# P03_McuPower.net
KiCad netlist of a schematic drawn in Altium Designer
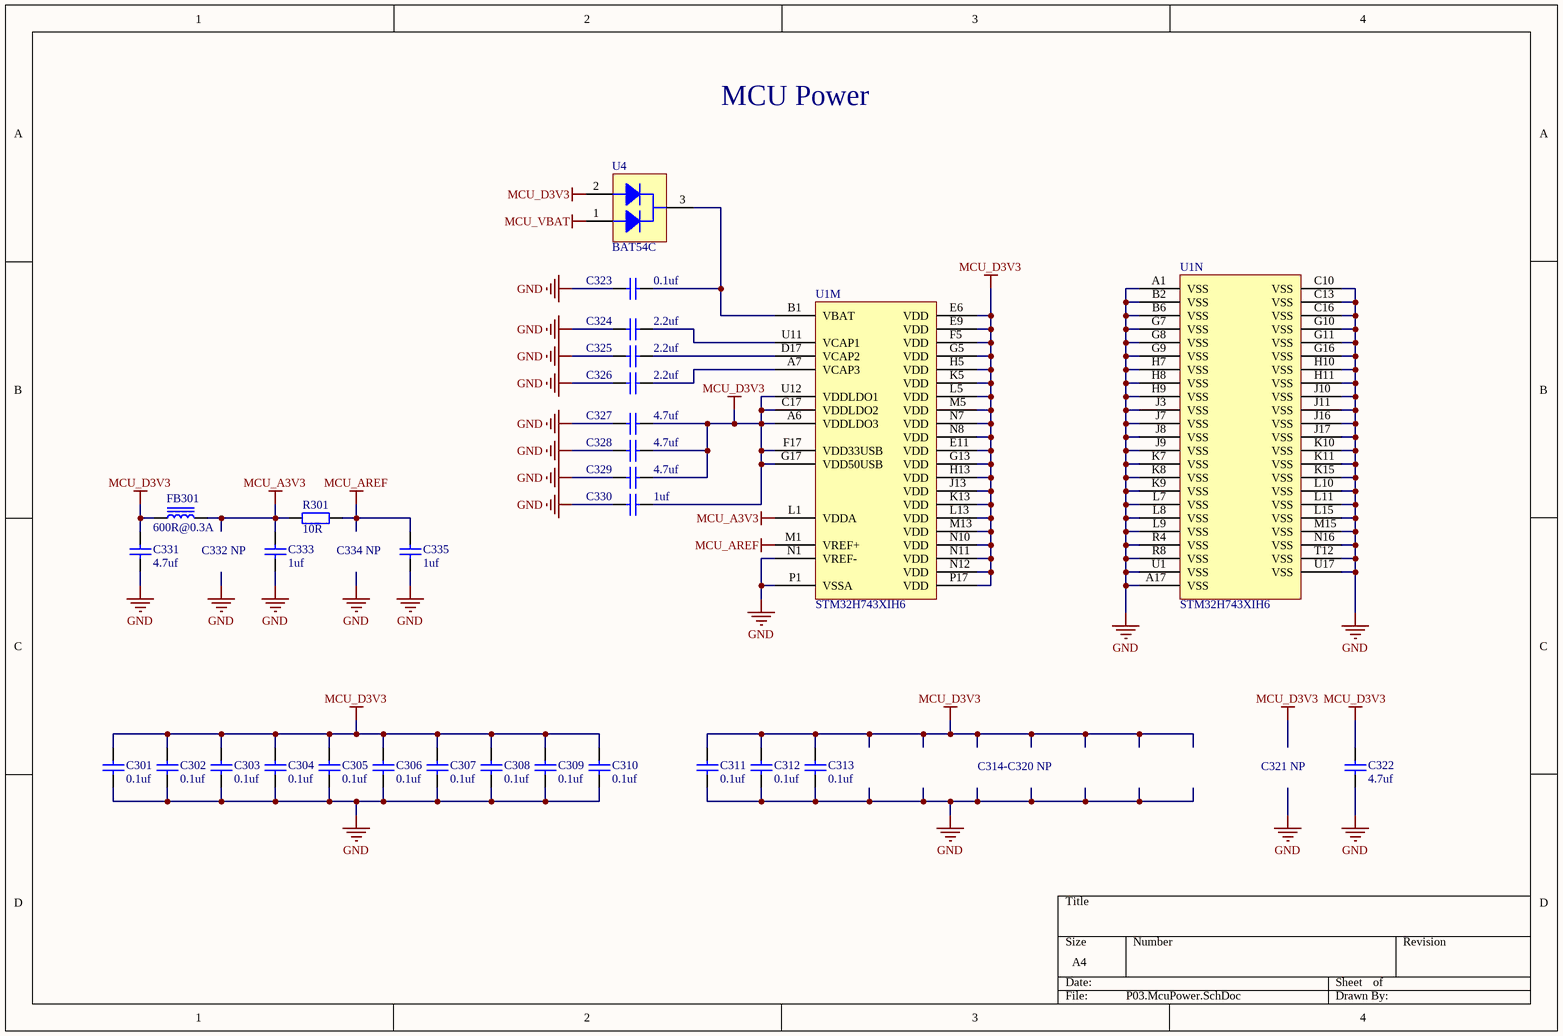
[diagram p0: P03.McuPower.SchDoc]

(export (version "E")
  (design (tool "Eeschema 10.0.6"))
  (components
    (comp (ref "C301")
      (value "0.1uf")
      (footprint "C0402")
      (fields (field (name "Comment") "Cap"))
      (libsource (lib "carrot_lib") (part "Cap"))
    )
    (comp (ref "C302")
      (value "0.1uf")
      (footprint "C0402")
      (fields (field (name "Comment") "Cap"))
      (libsource (lib "carrot_lib") (part "Cap"))
    )
    (comp (ref "C303")
      (value "0.1uf")
      (footprint "C0402")
      (fields (field (name "Comment") "Cap"))
      (libsource (lib "carrot_lib") (part "Cap"))
    )
    (comp (ref "C304")
      (value "0.1uf")
      (footprint "C0402")
      (fields (field (name "Comment") "Cap"))
      (libsource (lib "carrot_lib") (part "Cap"))
    )
    (comp (ref "C305")
      (value "0.1uf")
      (footprint "C0402")
      (fields (field (name "Comment") "Cap"))
      (libsource (lib "carrot_lib") (part "Cap"))
    )
    (comp (ref "C306")
      (value "0.1uf")
      (footprint "C0402")
      (fields (field (name "Comment") "Cap"))
      (libsource (lib "carrot_lib") (part "Cap"))
    )
    (comp (ref "C307")
      (value "0.1uf")
      (footprint "C0402")
      (fields (field (name "Comment") "Cap"))
      (libsource (lib "carrot_lib") (part "Cap"))
    )
    (comp (ref "C308")
      (value "0.1uf")
      (footprint "C0402")
      (fields (field (name "Comment") "Cap"))
      (libsource (lib "carrot_lib") (part "Cap"))
    )
    (comp (ref "C309")
      (value "0.1uf")
      (footprint "C0402")
      (fields (field (name "Comment") "Cap"))
      (libsource (lib "carrot_lib") (part "Cap"))
    )
    (comp (ref "C310")
      (value "0.1uf")
      (footprint "C0402")
      (fields (field (name "Comment") "Cap"))
      (libsource (lib "carrot_lib") (part "Cap"))
    )
    (comp (ref "C311")
      (value "0.1uf")
      (footprint "C0402")
      (fields (field (name "Comment") "Cap"))
      (libsource (lib "carrot_lib") (part "Cap"))
    )
    (comp (ref "C312")
      (value "0.1uf")
      (footprint "C0402")
      (fields (field (name "Comment") "Cap"))
      (libsource (lib "carrot_lib") (part "Cap"))
    )
    (comp (ref "C313")
      (value "0.1uf")
      (footprint "C0402")
      (fields (field (name "Comment") "Cap"))
      (libsource (lib "carrot_lib") (part "Cap"))
    )
    (comp (ref "C322")
      (value "4.7uf")
      (footprint "C0603")
      (fields (field (name "Comment") "Cap"))
      (libsource (lib "carrot_lib") (part "Cap"))
    )
    (comp (ref "C323")
      (value "0.1uf")
      (footprint "C0402")
      (fields (field (name "Comment") "Cap"))
      (libsource (lib "carrot_lib") (part "Cap"))
    )
    (comp (ref "C324")
      (value "2.2uf")
      (footprint "C0402")
      (fields (field (name "Comment") "Cap"))
      (libsource (lib "carrot_lib") (part "Cap"))
    )
    (comp (ref "C325")
      (value "2.2uf")
      (footprint "C0402")
      (fields (field (name "Comment") "Cap"))
      (libsource (lib "carrot_lib") (part "Cap"))
    )
    (comp (ref "C326")
      (value "2.2uf")
      (footprint "C0402")
      (fields (field (name "Comment") "Cap"))
      (libsource (lib "carrot_lib") (part "Cap"))
    )
    (comp (ref "C327")
      (value "4.7uf")
      (footprint "C0402")
      (fields (field (name "Comment") "Cap"))
      (libsource (lib "carrot_lib") (part "Cap"))
    )
    (comp (ref "C328")
      (value "4.7uf")
      (footprint "C0402")
      (fields (field (name "Comment") "Cap"))
      (libsource (lib "carrot_lib") (part "Cap"))
    )
    (comp (ref "C329")
      (value "4.7uf")
      (footprint "C0402")
      (fields (field (name "Comment") "Cap"))
      (libsource (lib "carrot_lib") (part "Cap"))
    )
    (comp (ref "C330")
      (value "1uf")
      (footprint "C0402")
      (fields (field (name "Comment") "Cap"))
      (libsource (lib "carrot_lib") (part "Cap"))
    )
    (comp (ref "C331")
      (value "4.7uf")
      (footprint "C0402")
      (fields (field (name "Comment") "Cap"))
      (libsource (lib "carrot_lib") (part "Cap"))
    )
    (comp (ref "C333")
      (value "1uf")
      (footprint "C0402")
      (fields (field (name "Comment") "Cap"))
      (libsource (lib "carrot_lib") (part "Cap"))
    )
    (comp (ref "C335")
      (value "1uf")
      (footprint "C0402")
      (fields (field (name "Comment") "Cap"))
      (libsource (lib "carrot_lib") (part "Cap"))
    )
    (comp (ref "FB301")
      (value "600R@0.3A")
      (footprint "FB0402")
      (description "Ferrite Bead")
      (libsource (lib "carrot_lib") (part "Ferrite Bead"))
    )
    (comp (ref "R301")
      (value "10R")
      (footprint "R0402")
      (description "电阻")
      (fields (field (name "Comment") "Res"))
      (libsource (lib "carrot_lib") (part "Res"))
    )
    (comp (ref "U1")
      (value "STM32H743XIH6")
      (footprint "STM32H743XIH6-TFBGA240+25")
      (description "32-bit Arm® Cortex®-M7 480MHz MCUs, up to 2MB Flash,up to 1MB RAM, 46 com. and analog interfaces")
      (libsource (lib "") (part "STM32H743XIH6_1"))
    )
    (comp (ref "U4")
      (value "BAT54C")
      (footprint "BAT54X-SOT23")
      (description "Schottky barrier diodes")
      (libsource (lib "carrot_lib") (part "BAT54C"))
    )
  )
  (nets
    (net (code "1") (name "GND") (class "Default")
      (node (ref "C301") (pin "1") (pinfunction "1_1") (pintype "passive"))
      (node (ref "C302") (pin "1") (pinfunction "1_1") (pintype "passive"))
      (node (ref "C303") (pin "1") (pinfunction "1_1") (pintype "passive"))
      (node (ref "C304") (pin "1") (pinfunction "1_1") (pintype "passive"))
      (node (ref "C305") (pin "1") (pinfunction "1_1") (pintype "passive"))
      (node (ref "C306") (pin "1") (pinfunction "1_1") (pintype "passive"))
      (node (ref "C307") (pin "1") (pinfunction "1_1") (pintype "passive"))
      (node (ref "C308") (pin "1") (pinfunction "1_1") (pintype "passive"))
      (node (ref "C309") (pin "1") (pinfunction "1_1") (pintype "passive"))
      (node (ref "C310") (pin "1") (pinfunction "1_1") (pintype "passive"))
      (node (ref "C311") (pin "1") (pinfunction "1_1") (pintype "passive"))
      (node (ref "C312") (pin "1") (pinfunction "1_1") (pintype "passive"))
      (node (ref "C313") (pin "1") (pinfunction "1_1") (pintype "passive"))
      (node (ref "C322") (pin "1") (pinfunction "1_1") (pintype "passive"))
      (node (ref "C323") (pin "1") (pinfunction "1_1") (pintype "passive"))
      (node (ref "C324") (pin "1") (pinfunction "1_1") (pintype "passive"))
      (node (ref "C325") (pin "1") (pinfunction "1_1") (pintype "passive"))
      (node (ref "C326") (pin "1") (pinfunction "1_1") (pintype "passive"))
      (node (ref "C327") (pin "1") (pinfunction "1_1") (pintype "passive"))
      (node (ref "C328") (pin "1") (pinfunction "1_1") (pintype "passive"))
      (node (ref "C329") (pin "1") (pinfunction "1_1") (pintype "passive"))
      (node (ref "C330") (pin "1") (pinfunction "1_1") (pintype "passive"))
      (node (ref "C331") (pin "1") (pinfunction "1_1") (pintype "passive"))
      (node (ref "C333") (pin "1") (pinfunction "1_1") (pintype "passive"))
      (node (ref "C335") (pin "1") (pinfunction "1_1") (pintype "passive"))
      (node (ref "U1") (pin "A1") (pinfunction "VSS_A1") (pintype "power_in"))
      (node (ref "U1") (pin "A17") (pinfunction "VSS_A17") (pintype "power_in"))
      (node (ref "U1") (pin "B2") (pinfunction "VSS_B2") (pintype "power_in"))
      (node (ref "U1") (pin "B6") (pinfunction "VSS_B6") (pintype "power_in"))
      (node (ref "U1") (pin "C10") (pinfunction "VSS_C10") (pintype "power_in"))
      (node (ref "U1") (pin "C13") (pinfunction "VSS_C13") (pintype "power_in"))
      (node (ref "U1") (pin "C16") (pinfunction "VSS_C16") (pintype "power_in"))
      (node (ref "U1") (pin "G10") (pinfunction "VSS_G10") (pintype "power_in"))
      (node (ref "U1") (pin "G11") (pinfunction "VSS_G11") (pintype "power_in"))
      (node (ref "U1") (pin "G16") (pinfunction "VSS_G16") (pintype "power_in"))
      (node (ref "U1") (pin "G7") (pinfunction "VSS_G7") (pintype "power_in"))
      (node (ref "U1") (pin "G8") (pinfunction "VSS_G8") (pintype "power_in"))
      (node (ref "U1") (pin "G9") (pinfunction "VSS_G9") (pintype "power_in"))
      (node (ref "U1") (pin "H10") (pinfunction "VSS_H10") (pintype "power_in"))
      (node (ref "U1") (pin "H11") (pinfunction "VSS_H11") (pintype "power_in"))
      (node (ref "U1") (pin "H7") (pinfunction "VSS_H7") (pintype "power_in"))
      (node (ref "U1") (pin "H8") (pinfunction "VSS_H8") (pintype "power_in"))
      (node (ref "U1") (pin "H9") (pinfunction "VSS_H9") (pintype "power_in"))
      (node (ref "U1") (pin "J10") (pinfunction "VSS_J10") (pintype "power_in"))
      (node (ref "U1") (pin "J11") (pinfunction "VSS_J11") (pintype "power_in"))
      (node (ref "U1") (pin "J16") (pinfunction "VSS_J16") (pintype "power_in"))
      (node (ref "U1") (pin "J17") (pinfunction "VSS_J17") (pintype "power_in"))
      (node (ref "U1") (pin "J3") (pinfunction "VSS_J3") (pintype "power_in"))
      (node (ref "U1") (pin "J7") (pinfunction "VSS_J7") (pintype "power_in"))
      (node (ref "U1") (pin "J8") (pinfunction "VSS_J8") (pintype "power_in"))
      (node (ref "U1") (pin "J9") (pinfunction "VSS_J9") (pintype "power_in"))
      (node (ref "U1") (pin "K10") (pinfunction "VSS_K10") (pintype "power_in"))
      (node (ref "U1") (pin "K11") (pinfunction "VSS_K11") (pintype "power_in"))
      (node (ref "U1") (pin "K15") (pinfunction "VSS_K15") (pintype "power_in"))
      (node (ref "U1") (pin "K7") (pinfunction "VSS_K7") (pintype "power_in"))
      (node (ref "U1") (pin "K8") (pinfunction "VSS_K8") (pintype "power_in"))
      (node (ref "U1") (pin "K9") (pinfunction "VSS_K9") (pintype "power_in"))
      (node (ref "U1") (pin "L10") (pinfunction "VSS_L10") (pintype "power_in"))
      (node (ref "U1") (pin "L11") (pinfunction "VSS_L11") (pintype "power_in"))
      (node (ref "U1") (pin "L15") (pinfunction "VSS_L15") (pintype "power_in"))
      (node (ref "U1") (pin "L7") (pinfunction "VSS_L7") (pintype "power_in"))
      (node (ref "U1") (pin "L8") (pinfunction "VSS_L8") (pintype "power_in"))
      (node (ref "U1") (pin "L9") (pinfunction "VSS_L9") (pintype "power_in"))
      (node (ref "U1") (pin "M15") (pinfunction "VSS_M15") (pintype "power_in"))
      (node (ref "U1") (pin "N1") (pinfunction "VREF-_N1") (pintype "power_in"))
      (node (ref "U1") (pin "N16") (pinfunction "VSS_N16") (pintype "power_in"))
      (node (ref "U1") (pin "P1") (pinfunction "VSSA_P1") (pintype "power_in"))
      (node (ref "U1") (pin "R4") (pinfunction "VSS_R4") (pintype "power_in"))
      (node (ref "U1") (pin "R8") (pinfunction "VSS_R8") (pintype "power_in"))
      (node (ref "U1") (pin "T12") (pinfunction "VSS_T12") (pintype "power_in"))
      (node (ref "U1") (pin "U1") (pinfunction "VSS_U1") (pintype "power_in"))
      (node (ref "U1") (pin "U17") (pinfunction "VSS_U17") (pintype "power_in"))
    )
    (net (code "2") (name "MCU_A3V3") (class "Default")
      (node (ref "C333") (pin "2") (pinfunction "2_2") (pintype "passive"))
      (node (ref "FB301") (pin "2") (pinfunction "2_2") (pintype "passive"))
      (node (ref "R301") (pin "1") (pinfunction "1_1") (pintype "passive"))
      (node (ref "U1") (pin "L1") (pinfunction "VDDA_L1") (pintype "power_in"))
    )
    (net (code "3") (name "MCU_AREF") (class "Default")
      (node (ref "C335") (pin "2") (pinfunction "2_2") (pintype "passive"))
      (node (ref "R301") (pin "2") (pinfunction "2_2") (pintype "passive"))
      (node (ref "U1") (pin "M1") (pinfunction "VREF+_M1") (pintype "power_in"))
    )
    (net (code "4") (name "MCU_D3V3") (class "Default")
      (node (ref "C301") (pin "2") (pinfunction "2_2") (pintype "passive"))
      (node (ref "C302") (pin "2") (pinfunction "2_2") (pintype "passive"))
      (node (ref "C303") (pin "2") (pinfunction "2_2") (pintype "passive"))
      (node (ref "C304") (pin "2") (pinfunction "2_2") (pintype "passive"))
      (node (ref "C305") (pin "2") (pinfunction "2_2") (pintype "passive"))
      (node (ref "C306") (pin "2") (pinfunction "2_2") (pintype "passive"))
      (node (ref "C307") (pin "2") (pinfunction "2_2") (pintype "passive"))
      (node (ref "C308") (pin "2") (pinfunction "2_2") (pintype "passive"))
      (node (ref "C309") (pin "2") (pinfunction "2_2") (pintype "passive"))
      (node (ref "C310") (pin "2") (pinfunction "2_2") (pintype "passive"))
      (node (ref "C311") (pin "2") (pinfunction "2_2") (pintype "passive"))
      (node (ref "C312") (pin "2") (pinfunction "2_2") (pintype "passive"))
      (node (ref "C313") (pin "2") (pinfunction "2_2") (pintype "passive"))
      (node (ref "C322") (pin "2") (pinfunction "2_2") (pintype "passive"))
      (node (ref "C327") (pin "2") (pinfunction "2_2") (pintype "passive"))
      (node (ref "C328") (pin "2") (pinfunction "2_2") (pintype "passive"))
      (node (ref "C329") (pin "2") (pinfunction "2_2") (pintype "passive"))
      (node (ref "C330") (pin "2") (pinfunction "2_2") (pintype "passive"))
      (node (ref "C331") (pin "2") (pinfunction "2_2") (pintype "passive"))
      (node (ref "FB301") (pin "1") (pinfunction "1_1") (pintype "passive"))
      (node (ref "U1") (pin "A6") (pinfunction "VDDLDO3_A6") (pintype "power_in"))
      (node (ref "U1") (pin "C17") (pinfunction "VDDLDO2_C17") (pintype "power_in"))
      (node (ref "U1") (pin "E11") (pinfunction "VDD_E11") (pintype "power_in"))
      (node (ref "U1") (pin "E6") (pinfunction "VDD_E6") (pintype "power_in"))
      (node (ref "U1") (pin "E9") (pinfunction "VDD_E9") (pintype "power_in"))
      (node (ref "U1") (pin "F17") (pinfunction "VDD33USB_F17") (pintype "power_in"))
      (node (ref "U1") (pin "F5") (pinfunction "VDD_F5") (pintype "power_in"))
      (node (ref "U1") (pin "G13") (pinfunction "VDD_G13") (pintype "power_in"))
      (node (ref "U1") (pin "G17") (pinfunction "VDD50USB_G17") (pintype "power_in"))
      (node (ref "U1") (pin "G5") (pinfunction "VDD_G5") (pintype "power_in"))
      (node (ref "U1") (pin "H13") (pinfunction "VDD_H13") (pintype "power_in"))
      (node (ref "U1") (pin "H5") (pinfunction "VDD_H5") (pintype "power_in"))
      (node (ref "U1") (pin "J13") (pinfunction "VDD_J13") (pintype "power_in"))
      (node (ref "U1") (pin "K13") (pinfunction "VDD_K13") (pintype "power_in"))
      (node (ref "U1") (pin "K5") (pinfunction "VDD_K5") (pintype "power_in"))
      (node (ref "U1") (pin "L13") (pinfunction "VDD_L13") (pintype "power_in"))
      (node (ref "U1") (pin "L5") (pinfunction "VDD_L5") (pintype "power_in"))
      (node (ref "U1") (pin "M13") (pinfunction "VDD_M13") (pintype "power_in"))
      (node (ref "U1") (pin "M5") (pinfunction "VDD_M5") (pintype "power_in"))
      (node (ref "U1") (pin "N10") (pinfunction "VDD_N10") (pintype "power_in"))
      (node (ref "U1") (pin "N11") (pinfunction "VDD_N11") (pintype "power_in"))
      (node (ref "U1") (pin "N12") (pinfunction "VDD_N12") (pintype "power_in"))
      (node (ref "U1") (pin "N7") (pinfunction "VDD_N7") (pintype "power_in"))
      (node (ref "U1") (pin "N8") (pinfunction "VDD_N8") (pintype "power_in"))
      (node (ref "U1") (pin "P17") (pinfunction "VDD_P17") (pintype "power_in"))
      (node (ref "U1") (pin "U12") (pinfunction "VDDLDO1_U12") (pintype "power_in"))
      (node (ref "U4") (pin "2") (pinfunction "2_2") (pintype "passive"))
    )
    (net (code "5") (name "MCU_VBAT") (class "Default")
      (node (ref "U4") (pin "1") (pinfunction "1_1") (pintype "passive"))
    )
    (net (code "6") (name "Net-(U1M-VBAT)") (class "Default")
      (node (ref "C323") (pin "2") (pinfunction "2_2") (pintype "passive"))
      (node (ref "U1") (pin "B1") (pinfunction "VBAT_B1") (pintype "power_in"))
      (node (ref "U4") (pin "3") (pinfunction "3_3") (pintype "passive"))
    )
    (net (code "7") (name "Net-(U1M-VCAP1)") (class "Default")
      (node (ref "C324") (pin "2") (pinfunction "2_2") (pintype "passive"))
      (node (ref "U1") (pin "U11") (pinfunction "VCAP1_U11") (pintype "passive"))
    )
    (net (code "8") (name "Net-(U1M-VCAP2)") (class "Default")
      (node (ref "C325") (pin "2") (pinfunction "2_2") (pintype "passive"))
      (node (ref "U1") (pin "D17") (pinfunction "VCAP2_D17") (pintype "passive"))
    )
    (net (code "9") (name "Net-(U1M-VCAP3)") (class "Default")
      (node (ref "C326") (pin "2") (pinfunction "2_2") (pintype "passive"))
      (node (ref "U1") (pin "A7") (pinfunction "VCAP3_A7") (pintype "passive"))
    )
  )
)
